# flasher.net
KiCad netlist of a schematic drawn in EAGLE
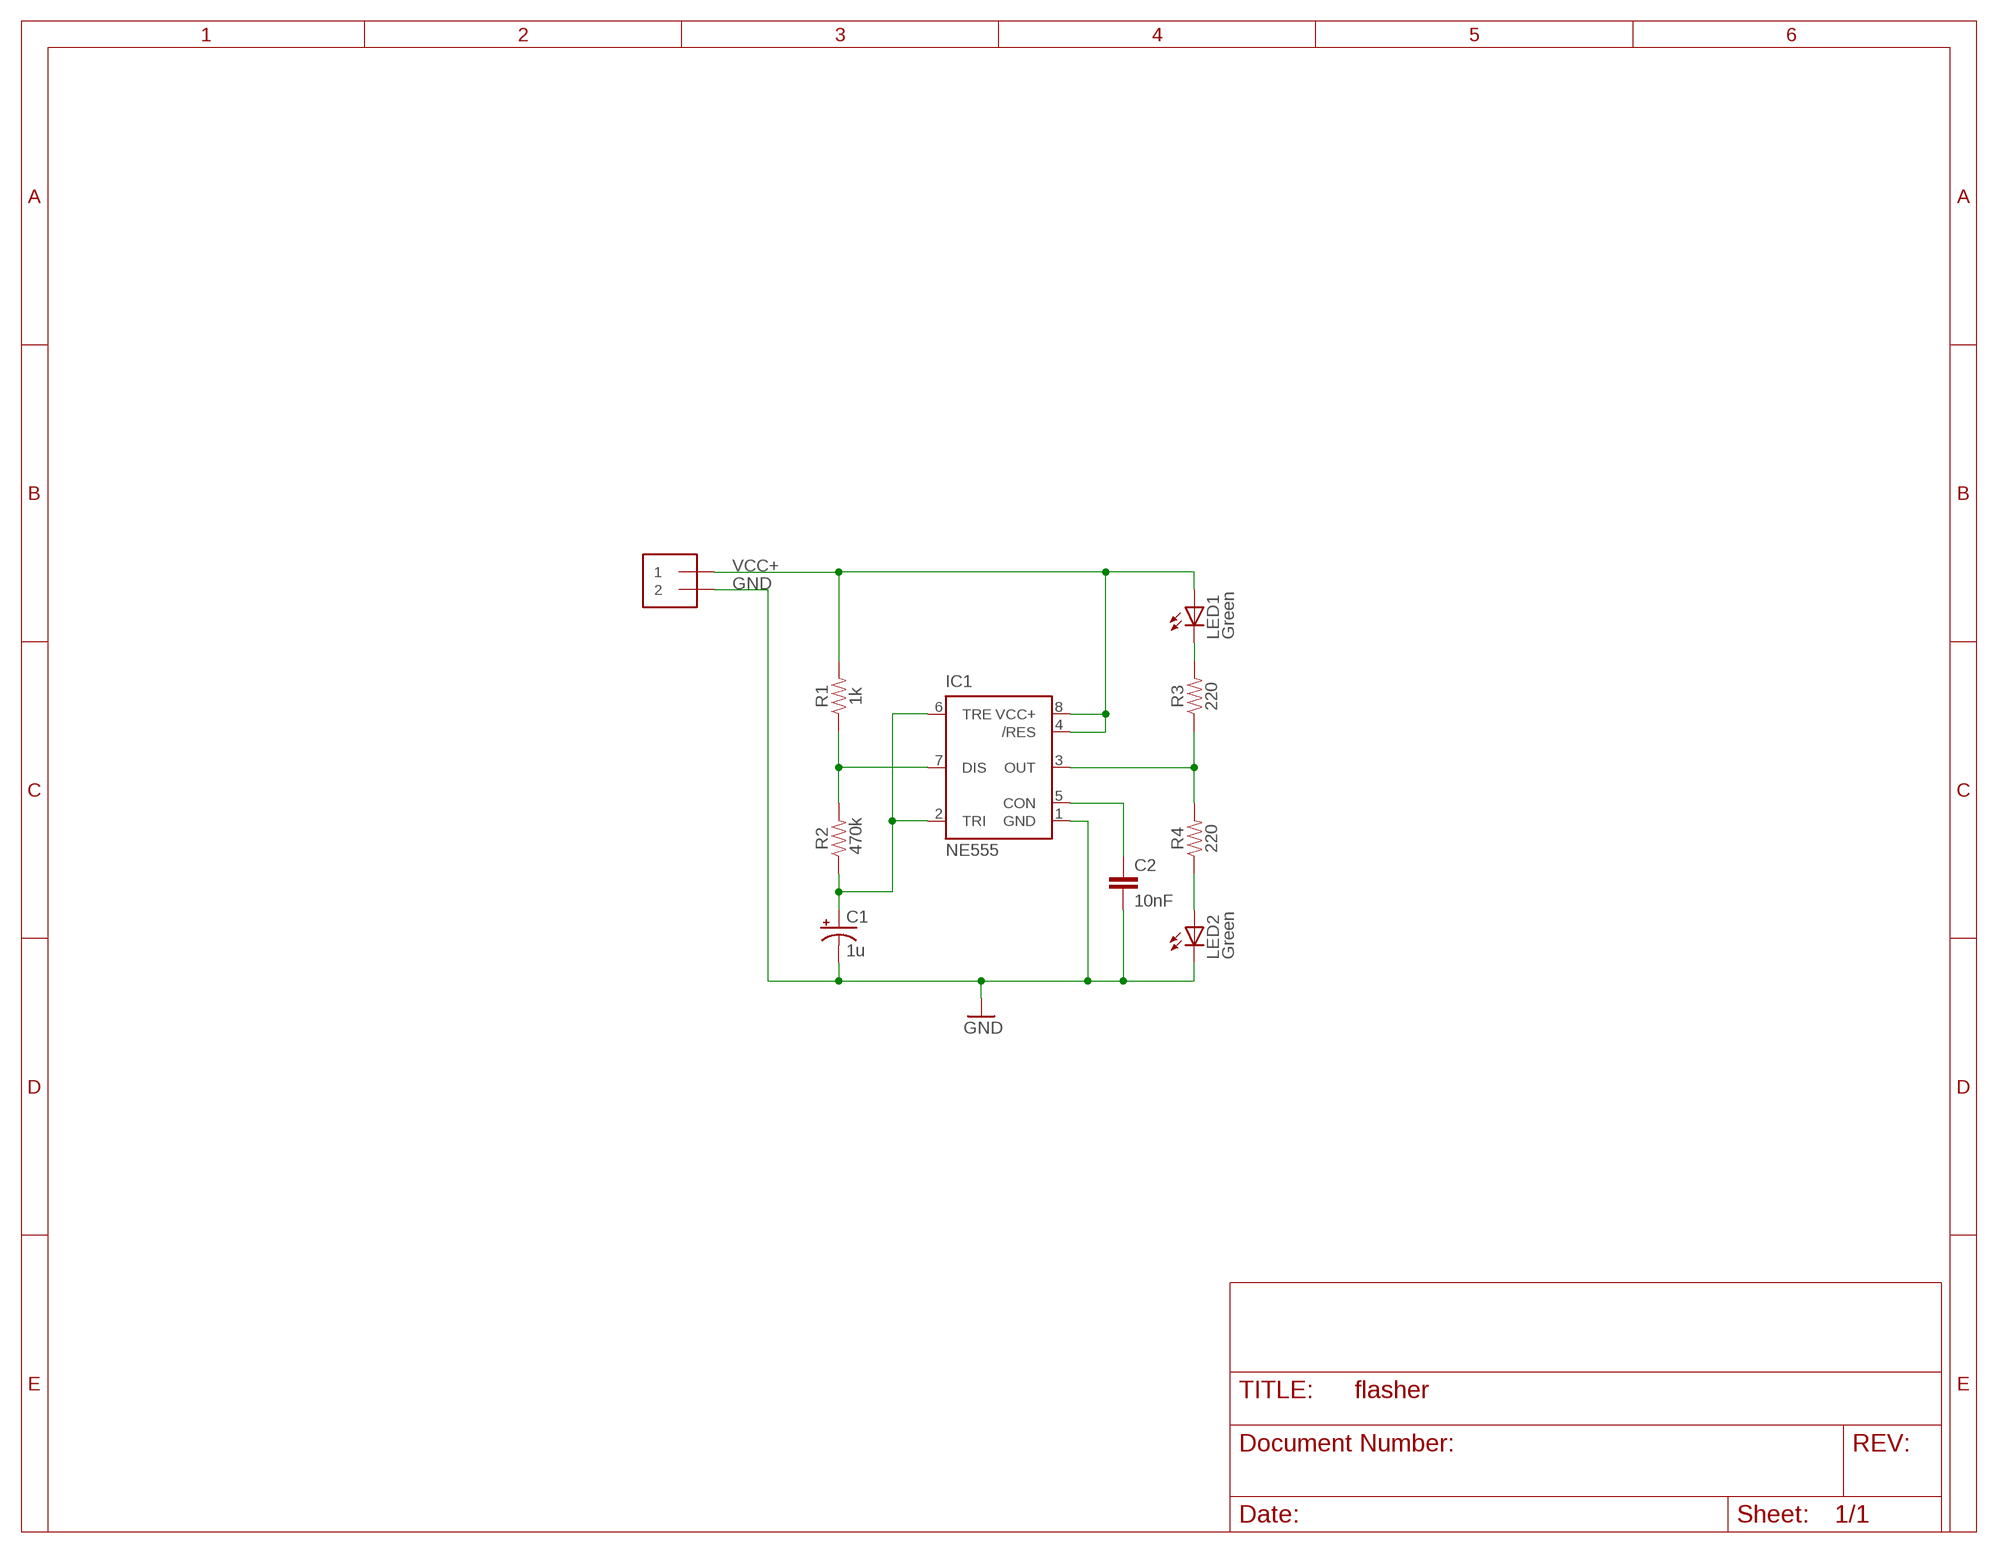
[diagram p0: schematic, sheet 1]

(export (version "E")
  (design (tool "Eeschema 10.0.6"))
  (components
    (comp (ref "C1")
      (value "1u")
      (footprint "eagle-import:E2,5-5")
      (libsource (lib "eagle-import") (part "CPOL-USE2.5-5"))
    )
    (comp (ref "C2")
      (value "10nF")
      (footprint "eagle-import:CAP-PTH-10MM")
      (libsource (lib "eagle-import") (part "10NF-PTH-10MM-10000V-1-%"))
    )
    (comp (ref "IC1")
      (value "NE555")
      (footprint "eagle-import:DIL-08")
      (fields (field (name "MF") "Arrow Electronics") (field (name "MPN") "NE555N"))
      (libsource (lib "eagle-import") (part "NE555"))
    )
    (comp (ref "J1")
      (value "1X2-3.5MM")
      (footprint "eagle-import:1X2-3.5MM")
      (libsource (lib "eagle-import") (part "1X2-3.5MM"))
    )
    (comp (ref "LED1")
      (value "Green")
      (footprint "eagle-import:LED5MM")
      (libsource (lib "eagle-import") (part "LED5MM"))
    )
    (comp (ref "LED2")
      (value "Green")
      (footprint "eagle-import:LED5MM")
      (libsource (lib "eagle-import") (part "LED5MM"))
    )
    (comp (ref "R1")
      (value "1k")
      (footprint "eagle-import:AXIAL-0.3")
      (libsource (lib "eagle-import") (part "1KOHM-HORIZ-1/4W-1%"))
    )
    (comp (ref "R2")
      (value "470k")
      (footprint "eagle-import:AXIAL-0.3")
      (libsource (lib "eagle-import") (part "RESISTORAXIAL-0.3"))
    )
    (comp (ref "R3")
      (value "220")
      (footprint "eagle-import:0603")
      (libsource (lib "eagle-import") (part "220OHM-0603-1/10W-1%"))
    )
    (comp (ref "R4")
      (value "220")
      (footprint "eagle-import:0603")
      (libsource (lib "eagle-import") (part "220OHM-0603-1/10W-1%"))
    )
  )
  (nets
    (net (code "1") (name "/VCC+") (class "Default")
      (node (ref "IC1") (pin "4") (pinfunction "/RES_4") (pintype "input"))
      (node (ref "IC1") (pin "8") (pinfunction "VCC+_8") (pintype "power_in"))
      (node (ref "J1") (pin "1") (pinfunction "1_1") (pintype "passive"))
      (node (ref "LED1") (pin "A") (pinfunction "A_A") (pintype "passive"))
      (node (ref "R1") (pin "P$2") (pinfunction "2_P$2") (pintype "passive"))
    )
    (net (code "2") (name "GND") (class "Default")
      (node (ref "C1") (pin "-") (pinfunction "-_-") (pintype "passive"))
      (node (ref "C2") (pin "2") (pinfunction "2_2") (pintype "passive"))
      (node (ref "IC1") (pin "1") (pinfunction "GND_1") (pintype "power_in"))
      (node (ref "J1") (pin "2") (pinfunction "2_2") (pintype "passive"))
      (node (ref "LED2") (pin "K") (pinfunction "C_K") (pintype "passive"))
    )
    (net (code "3") (name "Net-(IC1-CON)") (class "Default")
      (node (ref "C2") (pin "1") (pinfunction "1_1") (pintype "passive"))
      (node (ref "IC1") (pin "5") (pinfunction "CON_5") (pintype "input"))
    )
    (net (code "4") (name "Net-(IC1-DIS)") (class "Default")
      (node (ref "IC1") (pin "7") (pinfunction "DIS_7") (pintype "input"))
      (node (ref "R1") (pin "P$1") (pinfunction "1_P$1") (pintype "passive"))
      (node (ref "R2") (pin "P$2") (pinfunction "2_P$2") (pintype "passive"))
    )
    (net (code "5") (name "Net-(IC1-OUT)") (class "Default")
      (node (ref "IC1") (pin "3") (pinfunction "OUT_3") (pintype "output"))
      (node (ref "R3") (pin "1") (pinfunction "1_1") (pintype "passive"))
      (node (ref "R4") (pin "2") (pinfunction "2_2") (pintype "passive"))
    )
    (net (code "6") (name "Net-(IC1-TRE)") (class "Default")
      (node (ref "C1") (pin "+") (pinfunction "+_+") (pintype "passive"))
      (node (ref "IC1") (pin "2") (pinfunction "TRI_2") (pintype "input"))
      (node (ref "IC1") (pin "6") (pinfunction "TRE_6") (pintype "input"))
      (node (ref "R2") (pin "P$1") (pinfunction "1_P$1") (pintype "passive"))
    )
    (net (code "7") (name "Net-(LED1-C)") (class "Default")
      (node (ref "LED1") (pin "K") (pinfunction "C_K") (pintype "passive"))
      (node (ref "R3") (pin "2") (pinfunction "2_2") (pintype "passive"))
    )
    (net (code "8") (name "Net-(LED2-PadA)") (class "Default")
      (node (ref "LED2") (pin "A") (pinfunction "A_A") (pintype "passive"))
      (node (ref "R4") (pin "1") (pinfunction "1_1") (pintype "passive"))
    )
  )
)
